# do_an_2_1.net
KiCad netlist of a schematic drawn in EAGLE
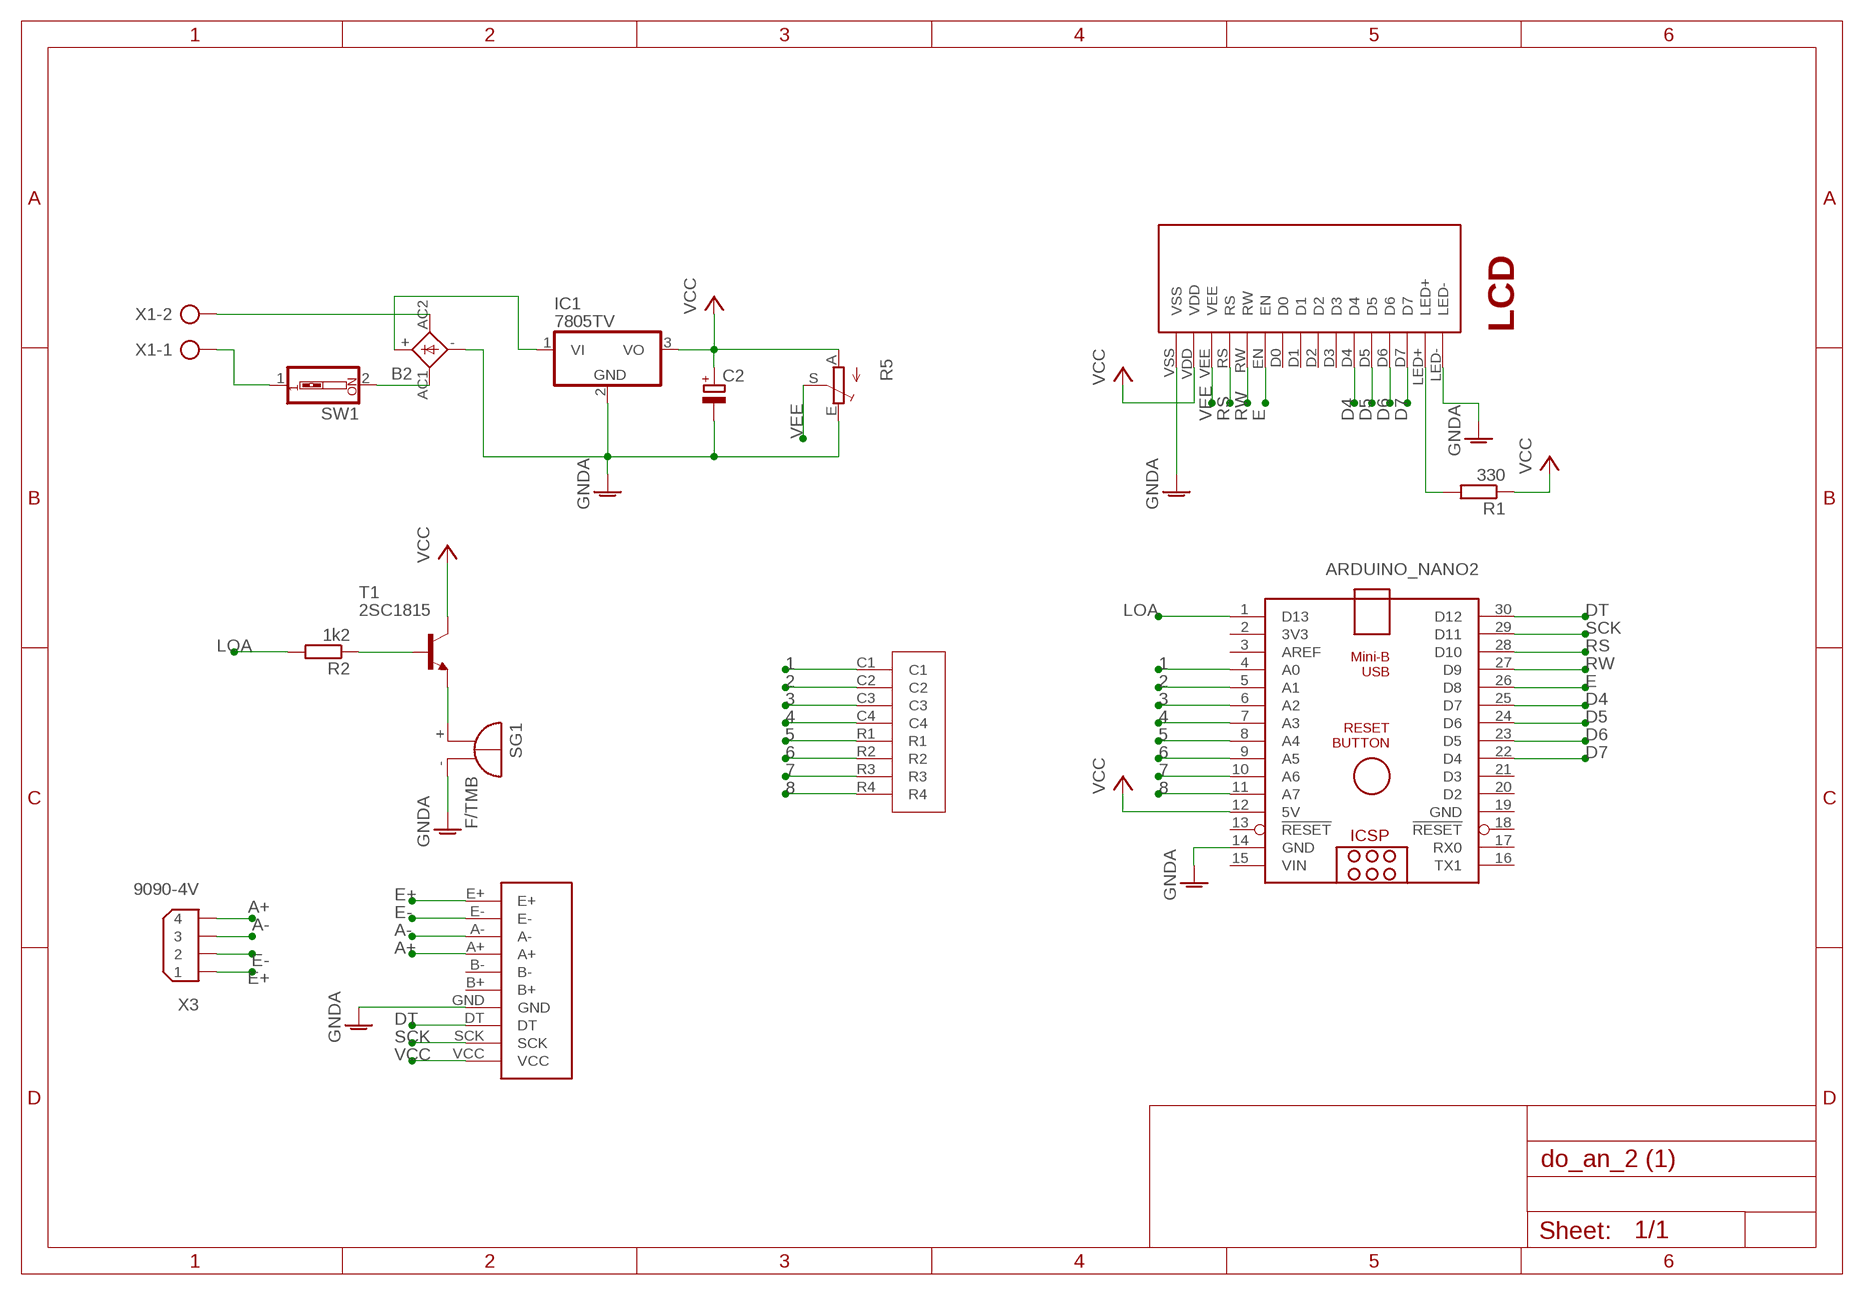
[diagram p0: schematic, sheet 1]

(export (version "E")
  (design (tool "Eeschema 10.0.6"))
  (components
    (comp (ref "ARDUINO_NANO2")
      (value "ARDUINO_NANO")
      (footprint "eagle-import:ARDUINO_NANO")
      (libsource (lib "eagle-import") (part "ARDUINO_NANO"))
    )
    (comp (ref "B2")
      (value "2KBP")
      (footprint "eagle-import:2KBP")
      (libsource (lib "eagle-import") (part "2KBP"))
    )
    (comp (ref "C2")
      (value "CPOL-EUE5-10.5")
      (footprint "eagle-import:E5-10,5")
      (libsource (lib "eagle-import") (part "CPOL-EUE5-10.5"))
    )
    (comp (ref "IC1")
      (value "7805TV")
      (footprint "eagle-import:TO220V")
      (libsource (lib "eagle-import") (part "78TV05"))
    )
    (comp (ref "R1")
      (value "330")
      (footprint "eagle-import:0207_10")
      (libsource (lib "eagle-import") (part "R-EU_0207/10"))
    )
    (comp (ref "R2")
      (value "1k2")
      (footprint "eagle-import:0207_10")
      (libsource (lib "eagle-import") (part "R-EU_0207/10"))
    )
    (comp (ref "R5")
      (value "TRIM_EU-S64W")
      (footprint "eagle-import:S64W")
      (libsource (lib "eagle-import") (part "TRIM_EU-S64W"))
    )
    (comp (ref "SG1")
      (value "F/TMB")
      (footprint "eagle-import:F_TMB")
      (libsource (lib "eagle-import") (part "F/TMB"))
    )
    (comp (ref "SW1")
      (value "SW_DIP-1")
      (footprint "eagle-import:EDG-01")
      (libsource (lib "eagle-import") (part "SW_DIP-1"))
    )
    (comp (ref "T1")
      (value "2SC1815")
      (footprint "eagle-import:TO92-ECB")
      (libsource (lib "eagle-import") (part "2SC1815"))
    )
    (comp (ref "U$1")
      (value "LCD20X4")
      (footprint "eagle-import:LCD20X4")
      (libsource (lib "eagle-import") (part "LCD20X4"))
    )
    (comp (ref "U$2")
      (value "MA_TRAN_PHIM")
      (footprint "eagle-import:MA_TRAN_PHIM")
      (libsource (lib "eagle-import") (part "MA_TRAN_PHIM"))
    )
    (comp (ref "U$3")
      (value "MACHMAUXANH")
      (footprint "eagle-import:MACHMAUXANH")
      (libsource (lib "eagle-import") (part "MACHMAUXANH"))
    )
    (comp (ref "X1")
      (value "AK300/2")
      (footprint "eagle-import:AK300_2")
      (libsource (lib "eagle-import") (part "AK300/2"))
    )
    (comp (ref "X3")
      (value "9090-4V")
      (footprint "eagle-import:9090-4V")
      (libsource (lib "eagle-import") (part "9090-4V"))
    )
  )
  (nets
    (net (code "1") (name "/1") (class "Default")
      (node (ref "ARDUINO_NANO2") (pin "4") (pinfunction "A0_4") (pintype "bidirectional"))
      (node (ref "U$2") (pin "C1") (pinfunction "C1_C1") (pintype "bidirectional"))
    )
    (net (code "2") (name "/2") (class "Default")
      (node (ref "ARDUINO_NANO2") (pin "5") (pinfunction "A1_5") (pintype "bidirectional"))
      (node (ref "U$2") (pin "C2") (pinfunction "C2_C2") (pintype "bidirectional"))
    )
    (net (code "3") (name "/3") (class "Default")
      (node (ref "ARDUINO_NANO2") (pin "6") (pinfunction "A2_6") (pintype "bidirectional"))
      (node (ref "U$2") (pin "C3") (pinfunction "C3_C3") (pintype "bidirectional"))
    )
    (net (code "4") (name "/4") (class "Default")
      (node (ref "ARDUINO_NANO2") (pin "7") (pinfunction "A3_7") (pintype "bidirectional"))
      (node (ref "U$2") (pin "C4") (pinfunction "C4_C4") (pintype "bidirectional"))
    )
    (net (code "5") (name "/5") (class "Default")
      (node (ref "ARDUINO_NANO2") (pin "8") (pinfunction "A4_8") (pintype "bidirectional"))
      (node (ref "U$2") (pin "R1") (pinfunction "R1_R1") (pintype "bidirectional"))
    )
    (net (code "6") (name "/6") (class "Default")
      (node (ref "ARDUINO_NANO2") (pin "9") (pinfunction "A5_9") (pintype "bidirectional"))
      (node (ref "U$2") (pin "R2") (pinfunction "R2_R2") (pintype "bidirectional"))
    )
    (net (code "7") (name "/7") (class "Default")
      (node (ref "ARDUINO_NANO2") (pin "10") (pinfunction "A6_10") (pintype "bidirectional"))
      (node (ref "U$2") (pin "R3") (pinfunction "R3_R3") (pintype "bidirectional"))
    )
    (net (code "8") (name "/8") (class "Default")
      (node (ref "ARDUINO_NANO2") (pin "11") (pinfunction "A7_11") (pintype "bidirectional"))
      (node (ref "U$2") (pin "R4") (pinfunction "R4_R4") (pintype "bidirectional"))
    )
    (net (code "9") (name "/A+") (class "Default")
      (node (ref "U$3") (pin "A+") (pinfunction "A+_A+") (pintype "bidirectional"))
      (node (ref "X3") (pin "4") (pinfunction "4_4") (pintype "passive"))
    )
    (net (code "10") (name "/A-") (class "Default")
      (node (ref "U$3") (pin "A-") (pinfunction "A-_A-") (pintype "bidirectional"))
      (node (ref "X3") (pin "3") (pinfunction "3_3") (pintype "passive"))
    )
    (net (code "11") (name "/D4") (class "Default")
      (node (ref "ARDUINO_NANO2") (pin "25") (pinfunction "D7_25") (pintype "bidirectional"))
      (node (ref "U$1") (pin "D4") (pinfunction "D4_D4") (pintype "bidirectional"))
    )
    (net (code "12") (name "/D5") (class "Default")
      (node (ref "ARDUINO_NANO2") (pin "24") (pinfunction "D6_24") (pintype "bidirectional"))
      (node (ref "U$1") (pin "D5") (pinfunction "D5_D5") (pintype "bidirectional"))
    )
    (net (code "13") (name "/D6") (class "Default")
      (node (ref "ARDUINO_NANO2") (pin "23") (pinfunction "D5_23") (pintype "bidirectional"))
      (node (ref "U$1") (pin "D6") (pinfunction "D6_D6") (pintype "bidirectional"))
    )
    (net (code "14") (name "/D7") (class "Default")
      (node (ref "ARDUINO_NANO2") (pin "22") (pinfunction "D4_22") (pintype "bidirectional"))
      (node (ref "U$1") (pin "D7") (pinfunction "D7_D7") (pintype "bidirectional"))
    )
    (net (code "15") (name "/DT") (class "Default")
      (node (ref "ARDUINO_NANO2") (pin "30") (pinfunction "D12_30") (pintype "bidirectional"))
      (node (ref "U$3") (pin "DT") (pinfunction "DT_DT") (pintype "bidirectional"))
    )
    (net (code "16") (name "/E") (class "Default")
      (node (ref "ARDUINO_NANO2") (pin "26") (pinfunction "D8_26") (pintype "bidirectional"))
      (node (ref "U$1") (pin "EN") (pinfunction "EN_EN") (pintype "bidirectional"))
    )
    (net (code "17") (name "/E+") (class "Default")
      (node (ref "U$3") (pin "E+") (pinfunction "E+_E+") (pintype "bidirectional"))
      (node (ref "X3") (pin "1") (pinfunction "1_1") (pintype "passive"))
    )
    (net (code "18") (name "/E-") (class "Default")
      (node (ref "U$3") (pin "E-") (pinfunction "E-_E-") (pintype "bidirectional"))
      (node (ref "X3") (pin "2") (pinfunction "2_2") (pintype "passive"))
    )
    (net (code "19") (name "/GND") (class "Default")
      (node (ref "ARDUINO_NANO2") (pin "19") (pinfunction "GND_19") (pintype "power_in"))
    )
    (net (code "20") (name "/LOA") (class "Default")
      (node (ref "ARDUINO_NANO2") (pin "1") (pinfunction "D13_1") (pintype "bidirectional"))
      (node (ref "R2") (pin "2") (pinfunction "2_2") (pintype "passive"))
    )
    (net (code "21") (name "/RS") (class "Default")
      (node (ref "ARDUINO_NANO2") (pin "28") (pinfunction "D10_28") (pintype "bidirectional"))
      (node (ref "U$1") (pin "RS") (pinfunction "RS_RS") (pintype "bidirectional"))
    )
    (net (code "22") (name "/RW") (class "Default")
      (node (ref "ARDUINO_NANO2") (pin "27") (pinfunction "D9_27") (pintype "bidirectional"))
      (node (ref "U$1") (pin "RW") (pinfunction "RW_RW") (pintype "bidirectional"))
    )
    (net (code "23") (name "/SCK") (class "Default")
      (node (ref "ARDUINO_NANO2") (pin "29") (pinfunction "D11_29") (pintype "bidirectional"))
      (node (ref "U$3") (pin "SCK") (pinfunction "SCK_SCK") (pintype "bidirectional"))
    )
    (net (code "24") (name "/VEE") (class "Default")
      (node (ref "R5") (pin "S") (pinfunction "S_S") (pintype "passive"))
      (node (ref "U$1") (pin "VEE") (pinfunction "VEE_VEE") (pintype "bidirectional"))
    )
    (net (code "25") (name "/VIN") (class "Default")
      (node (ref "ARDUINO_NANO2") (pin "15") (pinfunction "VIN_15") (pintype "power_in"))
    )
    (net (code "26") (name "GNDA") (class "Default")
      (node (ref "ARDUINO_NANO2") (pin "14") (pinfunction "GND_14") (pintype "power_in"))
      (node (ref "B2") (pin "-") (pinfunction "-_-") (pintype "passive"))
      (node (ref "C2") (pin "-") (pinfunction "-_-") (pintype "passive"))
      (node (ref "IC1") (pin "2") (pinfunction "GND_2") (pintype "passive"))
      (node (ref "R5") (pin "E") (pinfunction "E_E") (pintype "passive"))
      (node (ref "SG1") (pin "-") (pinfunction "-_-") (pintype "passive"))
      (node (ref "U$1") (pin "LED-") (pinfunction "LED-_LED-") (pintype "bidirectional"))
      (node (ref "U$1") (pin "VSS") (pinfunction "VSS_VSS") (pintype "bidirectional"))
      (node (ref "U$3") (pin "GND") (pinfunction "GND_GND") (pintype "bidirectional"))
    )
    (net (code "27") (name "Net-(B2-PadAC1)") (class "Default")
      (node (ref "B2") (pin "AC1") (pinfunction "AC1_AC1") (pintype "passive"))
      (node (ref "SW1") (pin "2") (pinfunction "2_2") (pintype "passive"))
    )
    (net (code "28") (name "Net-(IC1-VI)") (class "Default")
      (node (ref "B2") (pin "+") (pinfunction "+_+") (pintype "passive"))
      (node (ref "IC1") (pin "1") (pinfunction "VI_1") (pintype "input"))
    )
    (net (code "29") (name "Net-(R1-Pad2)") (class "Default")
      (node (ref "R1") (pin "2") (pinfunction "2_2") (pintype "passive"))
      (node (ref "U$1") (pin "LED+") (pinfunction "LED+_LED+") (pintype "bidirectional"))
    )
    (net (code "30") (name "Net-(R2-Pad1)") (class "Default")
      (node (ref "R2") (pin "1") (pinfunction "1_1") (pintype "passive"))
      (node (ref "T1") (pin "B") (pinfunction "B_B") (pintype "passive"))
    )
    (net (code "31") (name "Net-(SG1-Pad+)") (class "Default")
      (node (ref "SG1") (pin "+") (pinfunction "+_+") (pintype "passive"))
      (node (ref "T1") (pin "E") (pinfunction "E_E") (pintype "passive"))
    )
    (net (code "32") (name "Net-(X1A-KL)") (class "Default")
      (node (ref "SW1") (pin "1") (pinfunction "1_1") (pintype "passive"))
      (node (ref "X1") (pin "1") (pinfunction "KL_1") (pintype "passive"))
    )
    (net (code "33") (name "Net-(X1B-KL)") (class "Default")
      (node (ref "B2") (pin "AC2") (pinfunction "AC2_AC2") (pintype "passive"))
      (node (ref "X1") (pin "2") (pinfunction "KL_2") (pintype "passive"))
    )
    (net (code "34") (name "VCC") (class "Default")
      (node (ref "ARDUINO_NANO2") (pin "12") (pinfunction "5V_12") (pintype "power_in"))
      (node (ref "C2") (pin "+") (pinfunction "+_+") (pintype "passive"))
      (node (ref "IC1") (pin "3") (pinfunction "VO_3") (pintype "passive"))
      (node (ref "R1") (pin "1") (pinfunction "1_1") (pintype "passive"))
      (node (ref "R5") (pin "A") (pinfunction "A_A") (pintype "passive"))
      (node (ref "T1") (pin "C") (pinfunction "C_C") (pintype "passive"))
      (node (ref "U$1") (pin "VDD") (pinfunction "VDD_VDD") (pintype "bidirectional"))
      (node (ref "U$3") (pin "VCC") (pinfunction "VCC_VCC") (pintype "bidirectional"))
    )
    (net (code "35") (name "unconnected-(ARDUINO_NANO2-3V3-Pad2)") (class "Default")
      (node (ref "ARDUINO_NANO2") (pin "2") (pinfunction "3V3_2") (pintype "output"))
    )
    (net (code "36") (name "unconnected-(ARDUINO_NANO2-AREF-Pad3)") (class "Default")
      (node (ref "ARDUINO_NANO2") (pin "3") (pinfunction "AREF_3") (pintype "input"))
    )
    (net (code "37") (name "unconnected-(ARDUINO_NANO2-D2-Pad20)") (class "Default")
      (node (ref "ARDUINO_NANO2") (pin "20") (pinfunction "D2_20") (pintype "bidirectional"))
    )
    (net (code "38") (name "unconnected-(ARDUINO_NANO2-D3-Pad21)") (class "Default")
      (node (ref "ARDUINO_NANO2") (pin "21") (pinfunction "D3_21") (pintype "bidirectional"))
    )
    (net (code "39") (name "unconnected-(ARDUINO_NANO2-RX0-Pad17)") (class "Default")
      (node (ref "ARDUINO_NANO2") (pin "17") (pinfunction "RX0_17") (pintype "bidirectional"))
    )
    (net (code "40") (name "unconnected-(ARDUINO_NANO2-TX1-Pad16)") (class "Default")
      (node (ref "ARDUINO_NANO2") (pin "16") (pinfunction "TX1_16") (pintype "bidirectional"))
    )
    (net (code "41") (name "unconnected-(ARDUINO_NANO2-~{RESET}-Pad13)") (class "Default")
      (node (ref "ARDUINO_NANO2") (pin "13") (pinfunction "~{RESET}_13") (pintype "input"))
    )
    (net (code "42") (name "unconnected-(ARDUINO_NANO2-~{RESET}-Pad18)") (class "Default")
      (node (ref "ARDUINO_NANO2") (pin "18") (pinfunction "~{RESET}_18") (pintype "input"))
    )
    (net (code "43") (name "unconnected-(U$1-PadD0)") (class "Default")
      (node (ref "U$1") (pin "D0") (pinfunction "D0_D0") (pintype "bidirectional"))
    )
    (net (code "44") (name "unconnected-(U$1-PadD1)") (class "Default")
      (node (ref "U$1") (pin "D1") (pinfunction "D1_D1") (pintype "bidirectional"))
    )
    (net (code "45") (name "unconnected-(U$1-PadD2)") (class "Default")
      (node (ref "U$1") (pin "D2") (pinfunction "D2_D2") (pintype "bidirectional"))
    )
    (net (code "46") (name "unconnected-(U$1-PadD3)") (class "Default")
      (node (ref "U$1") (pin "D3") (pinfunction "D3_D3") (pintype "bidirectional"))
    )
    (net (code "47") (name "unconnected-(U$3-PadB+)") (class "Default")
      (node (ref "U$3") (pin "B+") (pinfunction "B+_B+") (pintype "bidirectional"))
    )
    (net (code "48") (name "unconnected-(U$3-PadB-)") (class "Default")
      (node (ref "U$3") (pin "B-") (pinfunction "B-_B-") (pintype "bidirectional"))
    )
  )
)
